# schematic.net
KiCad netlist of a schematic drawn in EasyEDA
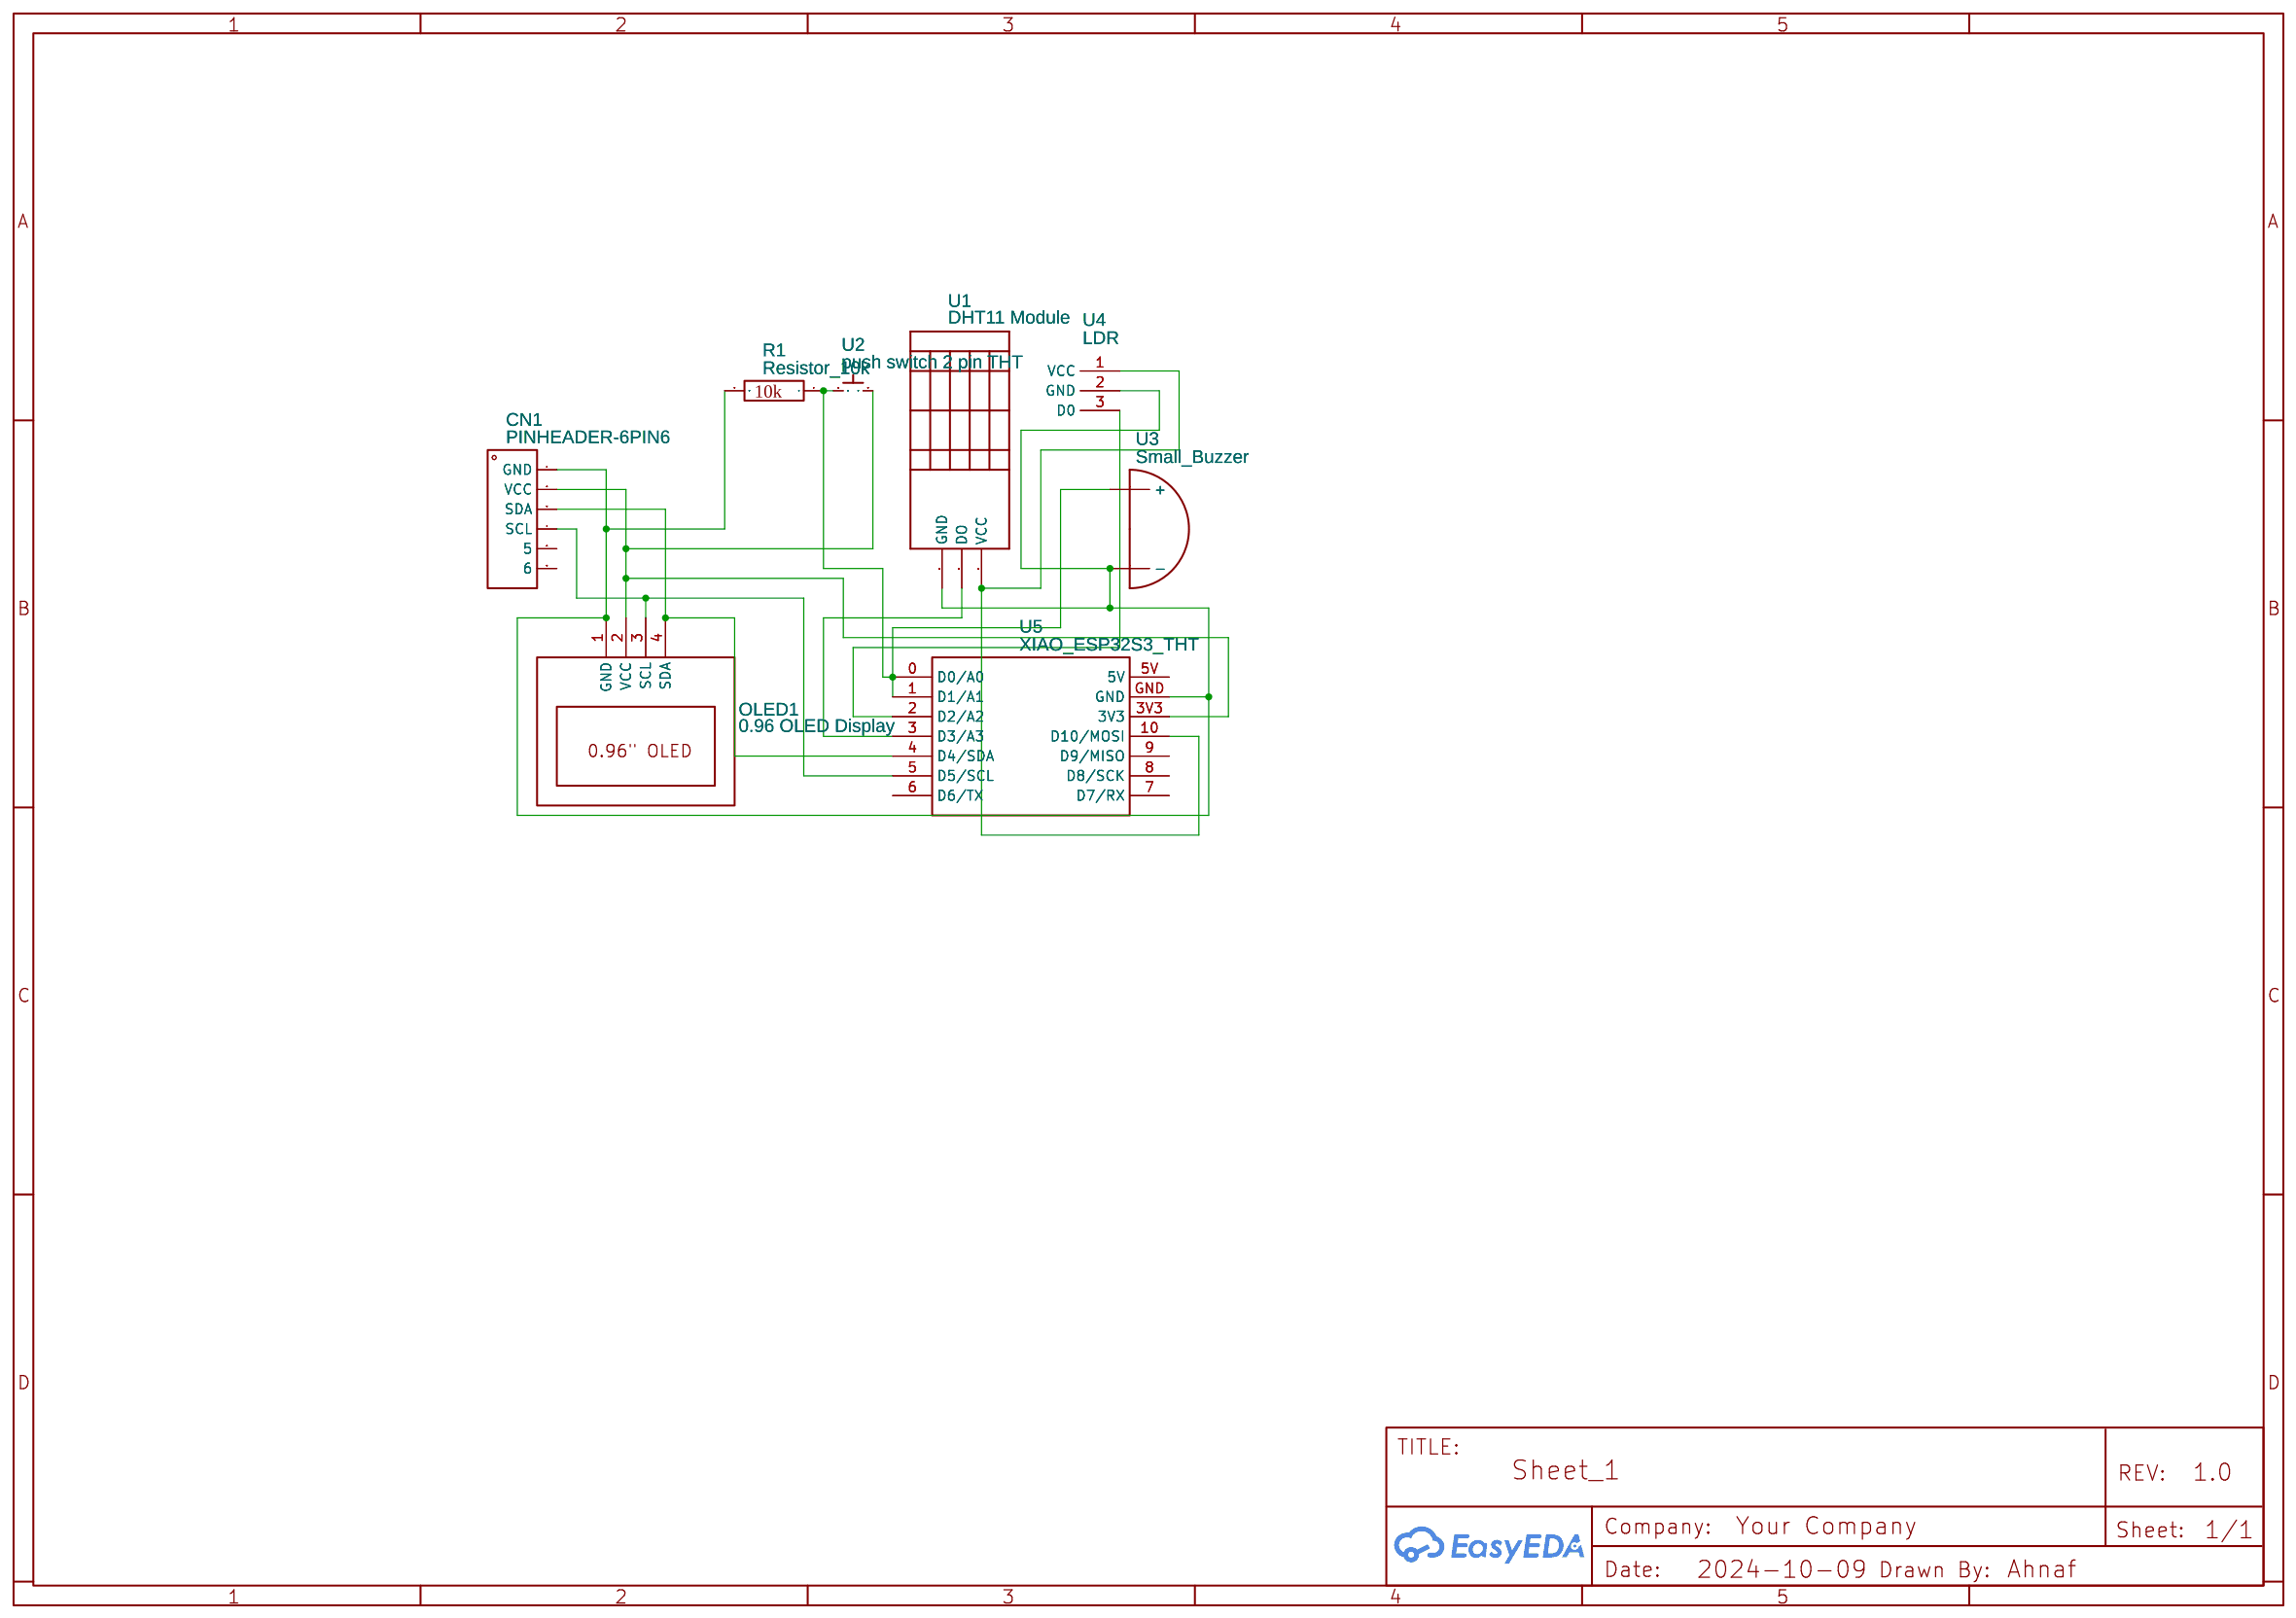
[diagram p0: schematic sheet]

(export (version "E")
  (design (tool "Eeschema 10.0.6"))
  (components
    (comp (ref "CN1") (value "PINHEADER-6PIN6") (libsource (lib "") (part "PINHEADER-6PIN6")))
    (comp (ref "OLED1")
      (value "0.96 OLED Display")
      (fields (field (name "Manufacturer Part") "0.96OLED_4P_MODULE_JX"))
      (libsource (lib "") (part "0.96OLED_4P_MODULE_JX"))
    )
    (comp (ref "R1") (value "Resistor_10k") (libsource (lib "") (part "Resistor_10k")))
    (comp (ref "U1") (value "DHT11 Module") (libsource (lib "") (part "DHT11 Module")))
    (comp (ref "U2") (value "push switch 2 pin THT") (libsource (lib "") (part "push switch 2 pin THT")))
    (comp (ref "U3") (value "Small_Buzzer") (libsource (lib "") (part "Small_Buzzer")))
    (comp (ref "U4") (value "LDR") (libsource (lib "") (part "3 pinheader")))
    (comp (ref "U5") (value "XIAO_ESP32S3_THT") (libsource (lib "") (part "XIAO_ESP32S3_THT")))
  )
  (nets
    (net (code "1") (name "Net-(CN1-GND)") (class "Default")
      (node (ref "CN1") (pin "1") (pinfunction "GND_1") (pintype "input"))
      (node (ref "OLED1") (pin "1") (pinfunction "GND_1") (pintype "unspecified"))
      (node (ref "R1") (pin "2") (pinfunction "2_2") (pintype "unspecified"))
      (node (ref "U1") (pin "GND") (pinfunction "GND_GND") (pintype "bidirectional"))
      (node (ref "U3") (pin "2") (pinfunction "-_2") (pintype "unspecified"))
      (node (ref "U4") (pin "2") (pinfunction "GND_2") (pintype "unspecified"))
      (node (ref "U5") (pin "GND") (pinfunction "GND_GND") (pintype "unspecified"))
    )
    (net (code "2") (name "Net-(CN1-SCL)") (class "Default")
      (node (ref "CN1") (pin "4") (pinfunction "SCL_4") (pintype "input"))
      (node (ref "OLED1") (pin "3") (pinfunction "SCL_3") (pintype "unspecified"))
      (node (ref "U5") (pin "5") (pinfunction "D5/SCL_5") (pintype "unspecified"))
    )
    (net (code "3") (name "Net-(CN1-SDA)") (class "Default")
      (node (ref "CN1") (pin "3") (pinfunction "SDA_3") (pintype "input"))
      (node (ref "OLED1") (pin "4") (pinfunction "SDA_4") (pintype "unspecified"))
      (node (ref "U5") (pin "4") (pinfunction "D4/SDA_4") (pintype "unspecified"))
    )
    (net (code "4") (name "Net-(CN1-VCC)") (class "Default")
      (node (ref "CN1") (pin "2") (pinfunction "VCC_2") (pintype "input"))
      (node (ref "OLED1") (pin "2") (pinfunction "VCC_2") (pintype "unspecified"))
      (node (ref "U2") (pin "2") (pinfunction "2_2") (pintype "unspecified"))
      (node (ref "U5") (pin "3V3") (pinfunction "3V3_3V3") (pintype "unspecified"))
    )
    (net (code "5") (name "Net-(U3-+)") (class "Default")
      (node (ref "R1") (pin "1") (pinfunction "1_1") (pintype "unspecified"))
      (node (ref "U2") (pin "1") (pinfunction "1_1") (pintype "unspecified"))
      (node (ref "U3") (pin "1") (pinfunction "+_1") (pintype "unspecified"))
      (node (ref "U5") (pin "0") (pinfunction "D0/A0_0") (pintype "unspecified"))
      (node (ref "U5") (pin "1") (pinfunction "D1/A1_1") (pintype "unspecified"))
    )
    (net (code "6") (name "Net-(U4-D0)") (class "Default")
      (node (ref "U4") (pin "3") (pinfunction "D0_3") (pintype "unspecified"))
      (node (ref "U5") (pin "2") (pinfunction "D2/A2_2") (pintype "unspecified"))
    )
    (net (code "7") (name "Net-(U4-VCC)") (class "Default")
      (node (ref "U1") (pin "VCC") (pinfunction "VCC_VCC") (pintype "bidirectional"))
      (node (ref "U4") (pin "1") (pinfunction "VCC_1") (pintype "unspecified"))
      (node (ref "U5") (pin "10") (pinfunction "D10/MOSI_10") (pintype "unspecified"))
    )
    (net (code "8") (name "Net-(U5-D3{slash}A3)") (class "Default")
      (node (ref "U1") (pin "DO") (pinfunction "DO_DO") (pintype "bidirectional"))
      (node (ref "U5") (pin "3") (pinfunction "D3/A3_3") (pintype "unspecified"))
    )
    (net (code "9") (name "unconnected-(CN1-Pad5)") (class "Default")
      (node (ref "CN1") (pin "5") (pinfunction "5_5") (pintype "input"))
    )
    (net (code "10") (name "unconnected-(CN1-Pad6)") (class "Default")
      (node (ref "CN1") (pin "6") (pinfunction "6_6") (pintype "input"))
    )
    (net (code "11") (name "unconnected-(U5-D6{slash}TX-Pad6)") (class "Default")
      (node (ref "U5") (pin "6") (pinfunction "D6/TX_6") (pintype "unspecified"))
    )
    (net (code "12") (name "unconnected-(U5-D7{slash}RX-Pad7)") (class "Default")
      (node (ref "U5") (pin "7") (pinfunction "D7/RX_7") (pintype "unspecified"))
    )
    (net (code "13") (name "unconnected-(U5-D8{slash}SCK-Pad8)") (class "Default")
      (node (ref "U5") (pin "8") (pinfunction "D8/SCK_8") (pintype "unspecified"))
    )
    (net (code "14") (name "unconnected-(U5-D9{slash}MISO-Pad9)") (class "Default")
      (node (ref "U5") (pin "9") (pinfunction "D9/MISO_9") (pintype "unspecified"))
    )
    (net (code "15") (name "unconnected-(U5-Pad5V)") (class "Default")
      (node (ref "U5") (pin "5V") (pinfunction "5V_5V") (pintype "unspecified"))
    )
  )
)
